# cdrbot.net
KiCad netlist of a schematic drawn in EAGLE
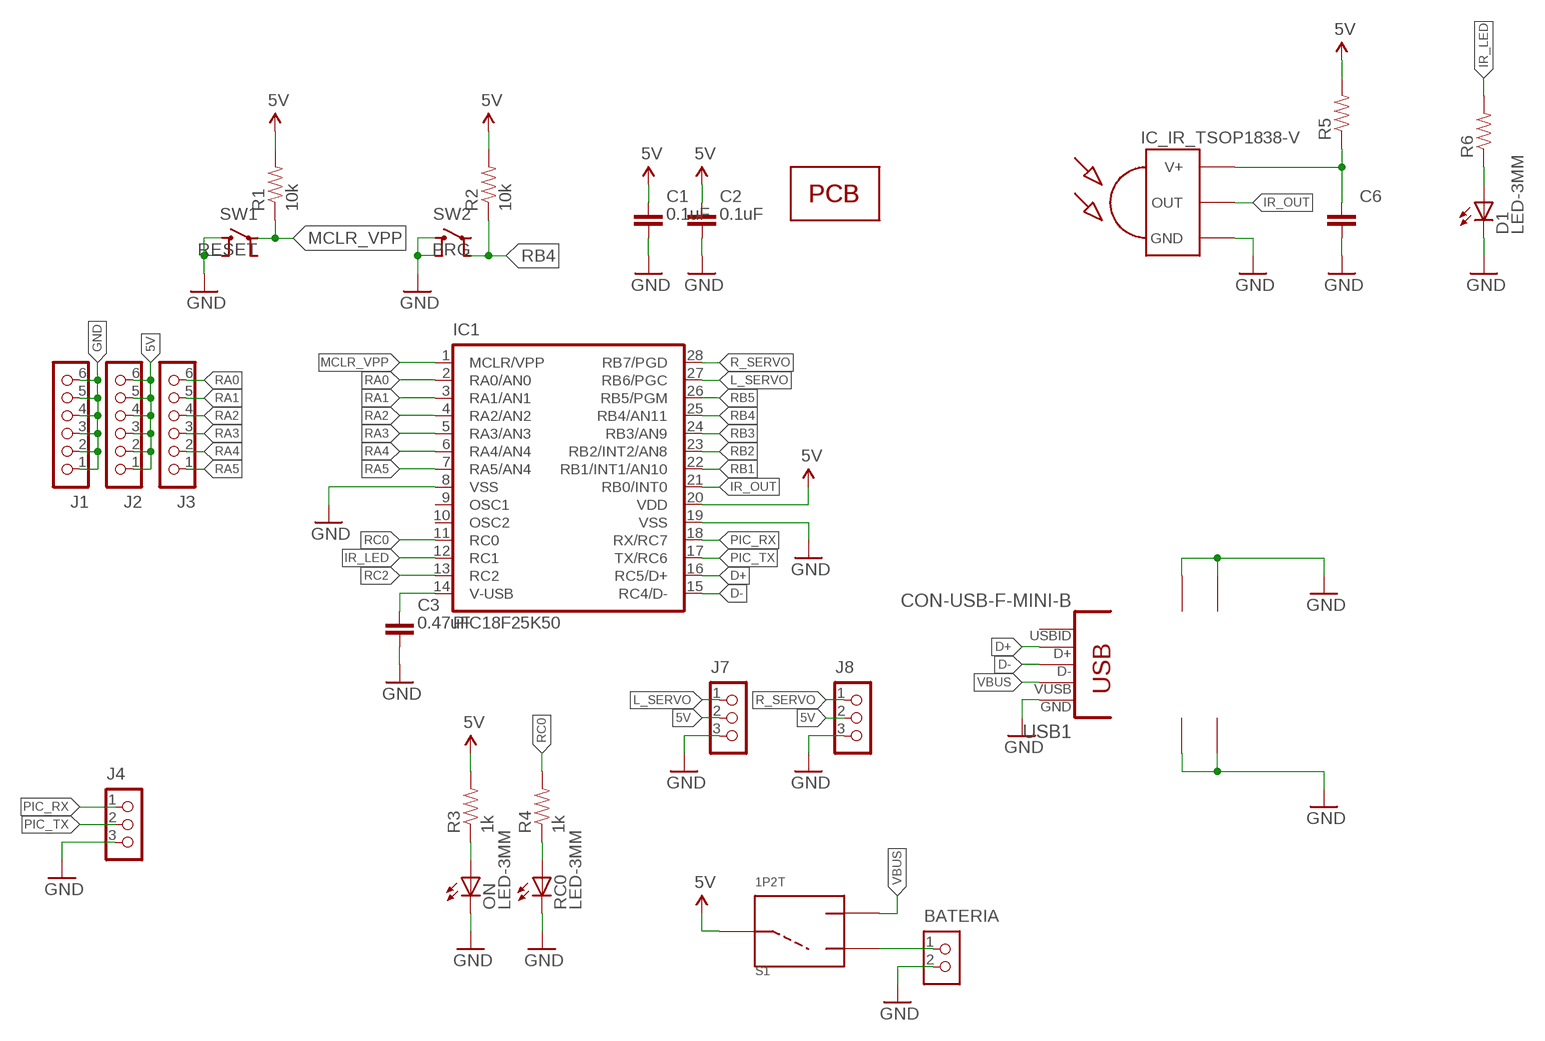
[diagram p0: schematic, sheet 1]

(export (version "E")
  (design (tool "Eeschema 10.0.6"))
  (components
    (comp (ref "BATERIA")
      (value "CON_HEADER_1X02-PTH-M")
      (footprint "eagle-import:M1X02_M")
      (libsource (lib "eagle-import") (part "CON_HEADER_1X02-PTH-M"))
    )
    (comp (ref "C1")
      (value "0.1uF")
      (footprint "eagle-import:C025-025X050")
      (libsource (lib "eagle-import") (part "CAPACITOR-DECOUPLING"))
    )
    (comp (ref "C2")
      (value "0.1uF")
      (footprint "eagle-import:C025-025X050")
      (libsource (lib "eagle-import") (part "CAPACITOR-DECOUPLING"))
    )
    (comp (ref "C3")
      (value "0.47uF")
      (footprint "eagle-import:C025-025X050")
      (libsource (lib "eagle-import") (part "CAPACITOR-DECOUPLING"))
    )
    (comp (ref "C6")
      (value "CAPACITOR-DECOUPLING")
      (footprint "eagle-import:C025-025X050")
      (libsource (lib "eagle-import") (part "CAPACITOR-DECOUPLING"))
    )
    (comp (ref "D1")
      (value "LED-3MM")
      (footprint "eagle-import:LED-3MM")
      (libsource (lib "eagle-import") (part "LED-3MM"))
    )
    (comp (ref "IC1")
      (value "PIC18F25K50")
      (footprint "eagle-import:DIL-28")
      (libsource (lib "eagle-import") (part "PIC18F2550"))
    )
    (comp (ref "IC2")
      (value "IC_IR_TSOP1838-V")
      (footprint "eagle-import:TSOP18XX_V")
      (libsource (lib "eagle-import") (part "IC_IR_TSOP1838-V"))
    )
    (comp (ref "J1")
      (value "CON_HEADER_1X06-PTH_M")
      (footprint "eagle-import:M1X06_M")
      (libsource (lib "eagle-import") (part "CON_HEADER_1X06-PTH_M"))
    )
    (comp (ref "J2")
      (value "CON_HEADER_1X06-PTH_M")
      (footprint "eagle-import:M1X06_M")
      (libsource (lib "eagle-import") (part "CON_HEADER_1X06-PTH_M"))
    )
    (comp (ref "J3")
      (value "CON_HEADER_1X06-PTH_M")
      (footprint "eagle-import:M1X06_M")
      (libsource (lib "eagle-import") (part "CON_HEADER_1X06-PTH_M"))
    )
    (comp (ref "J4")
      (value "CON_HEADER_1X03-PTH_M")
      (footprint "eagle-import:M1X03_M")
      (libsource (lib "eagle-import") (part "CON_HEADER_1X03-PTH_M"))
    )
    (comp (ref "J7")
      (value "CON_HEADER_1X03-PTH_M")
      (footprint "eagle-import:M1X03_M")
      (libsource (lib "eagle-import") (part "CON_HEADER_1X03-PTH_M"))
    )
    (comp (ref "J8")
      (value "CON_HEADER_1X03-PTH_M")
      (footprint "eagle-import:M1X03_M")
      (libsource (lib "eagle-import") (part "CON_HEADER_1X03-PTH_M"))
    )
    (comp (ref "ON")
      (value "LED-3MM")
      (footprint "eagle-import:LED-3MM")
      (libsource (lib "eagle-import") (part "LED-3MM"))
    )
    (comp (ref "PCB1")
      (value "PCB_DP_SQUARE-5X5")
      (footprint "eagle-import:PCB5X5")
      (libsource (lib "eagle-import") (part "PCB_DP_SQUARE-5X5"))
    )
    (comp (ref "R1")
      (value "10k")
      (footprint "eagle-import:RTH025W_03")
      (libsource (lib "eagle-import") (part "RESISTOR-1/4W-0.3{dblquote}"))
    )
    (comp (ref "R2")
      (value "10k")
      (footprint "eagle-import:RTH025W_03")
      (libsource (lib "eagle-import") (part "RESISTOR-1/4W-0.3{dblquote}"))
    )
    (comp (ref "R3")
      (value "1k")
      (footprint "eagle-import:RTH025W_03")
      (libsource (lib "eagle-import") (part "RESISTOR-1/4W-0.3{dblquote}"))
    )
    (comp (ref "R4")
      (value "1k")
      (footprint "eagle-import:RTH025W_03")
      (libsource (lib "eagle-import") (part "RESISTOR-1/4W-0.3{dblquote}"))
    )
    (comp (ref "R5")
      (value "RESISTOR-1/4W-0.3\"")
      (footprint "eagle-import:RTH025W_03")
      (libsource (lib "eagle-import") (part "RESISTOR-1/4W-0.3{dblquote}"))
    )
    (comp (ref "R6")
      (value "RESISTOR-1/4W-0.3\"")
      (footprint "eagle-import:RTH025W_03")
      (libsource (lib "eagle-import") (part "RESISTOR-1/4W-0.3{dblquote}"))
    )
    (comp (ref "RC0")
      (value "LED-3MM")
      (footprint "eagle-import:LED-3MM")
      (libsource (lib "eagle-import") (part "LED-3MM"))
    )
    (comp (ref "S1")
      (value "1P2T")
      (footprint "eagle-import:1P2T")
      (libsource (lib "eagle-import") (part "1P2T"))
    )
    (comp (ref "SW1")
      (value "RESET")
      (footprint "eagle-import:TACTILE-PTH")
      (libsource (lib "eagle-import") (part "SWITCH-MOMPTH"))
    )
    (comp (ref "SW2")
      (value "PRG")
      (footprint "eagle-import:TACTILE-PTH")
      (libsource (lib "eagle-import") (part "SWITCH-MOMPTH"))
    )
    (comp (ref "USB1")
      (value "CON-USB-F-MINI-B")
      (footprint "eagle-import:CONN_USB_MINI-B")
      (libsource (lib "eagle-import") (part "CON-USB-F-MINI-B"))
    )
  )
  (nets
    (net (code "1") (name "5V") (class "Default")
      (node (ref "C1") (pin "1") (pinfunction "1_1") (pintype "passive"))
      (node (ref "C2") (pin "1") (pinfunction "1_1") (pintype "passive"))
      (node (ref "IC1") (pin "20") (pinfunction "VDD_20") (pintype "power_in"))
      (node (ref "J2") (pin "1") (pinfunction "1_1") (pintype "bidirectional"))
      (node (ref "J2") (pin "2") (pinfunction "2_2") (pintype "bidirectional"))
      (node (ref "J2") (pin "3") (pinfunction "3_3") (pintype "bidirectional"))
      (node (ref "J2") (pin "4") (pinfunction "4_4") (pintype "bidirectional"))
      (node (ref "J2") (pin "5") (pinfunction "5_5") (pintype "bidirectional"))
      (node (ref "J2") (pin "6") (pinfunction "6_6") (pintype "bidirectional"))
      (node (ref "J7") (pin "2") (pinfunction "2_2") (pintype "bidirectional"))
      (node (ref "J8") (pin "2") (pinfunction "2_2") (pintype "bidirectional"))
      (node (ref "R1") (pin "2") (pinfunction "2_2") (pintype "passive"))
      (node (ref "R2") (pin "2") (pinfunction "2_2") (pintype "passive"))
      (node (ref "R3") (pin "2") (pinfunction "2_2") (pintype "passive"))
      (node (ref "R5") (pin "2") (pinfunction "2_2") (pintype "passive"))
      (node (ref "S1") (pin "P$1") (pinfunction "P$1_P$1") (pintype "bidirectional"))
    )
    (net (code "2") (name "D+") (class "Default")
      (node (ref "IC1") (pin "16") (pinfunction "RC5/D+_16") (pintype "bidirectional"))
      (node (ref "USB1") (pin "D+") (pinfunction "D+_D+") (pintype "bidirectional"))
    )
    (net (code "3") (name "D-") (class "Default")
      (node (ref "IC1") (pin "15") (pinfunction "RC4/D-_15") (pintype "bidirectional"))
      (node (ref "USB1") (pin "D-") (pinfunction "D-_D-") (pintype "bidirectional"))
    )
    (net (code "4") (name "GND") (class "Default")
      (node (ref "BATERIA") (pin "2") (pinfunction "2_2") (pintype "bidirectional"))
      (node (ref "C1") (pin "2") (pinfunction "2_2") (pintype "passive"))
      (node (ref "C2") (pin "2") (pinfunction "2_2") (pintype "passive"))
      (node (ref "C3") (pin "2") (pinfunction "2_2") (pintype "passive"))
      (node (ref "C6") (pin "2") (pinfunction "2_2") (pintype "passive"))
      (node (ref "D1") (pin "K") (pinfunction "C_K") (pintype "passive"))
      (node (ref "IC1") (pin "19") (pinfunction "VSS_19") (pintype "power_in"))
      (node (ref "IC1") (pin "8") (pinfunction "VSS_8") (pintype "power_in"))
      (node (ref "IC2") (pin "GND") (pinfunction "GND_GND") (pintype "bidirectional"))
      (node (ref "J1") (pin "1") (pinfunction "1_1") (pintype "bidirectional"))
      (node (ref "J1") (pin "2") (pinfunction "2_2") (pintype "bidirectional"))
      (node (ref "J1") (pin "3") (pinfunction "3_3") (pintype "bidirectional"))
      (node (ref "J1") (pin "4") (pinfunction "4_4") (pintype "bidirectional"))
      (node (ref "J1") (pin "5") (pinfunction "5_5") (pintype "bidirectional"))
      (node (ref "J1") (pin "6") (pinfunction "6_6") (pintype "bidirectional"))
      (node (ref "J4") (pin "3") (pinfunction "3_3") (pintype "bidirectional"))
      (node (ref "J7") (pin "3") (pinfunction "3_3") (pintype "bidirectional"))
      (node (ref "J8") (pin "3") (pinfunction "3_3") (pintype "bidirectional"))
      (node (ref "ON") (pin "K") (pinfunction "C_K") (pintype "passive"))
      (node (ref "RC0") (pin "K") (pinfunction "C_K") (pintype "passive"))
      (node (ref "SW1") (pin "3") (pinfunction "2_3") (pintype "passive"))
      (node (ref "SW1") (pin "4") (pinfunction "4_4") (pintype "passive"))
      (node (ref "SW2") (pin "3") (pinfunction "2_3") (pintype "passive"))
      (node (ref "SW2") (pin "4") (pinfunction "4_4") (pintype "passive"))
      (node (ref "USB1") (pin "BODY@1") (pinfunction "BODY_BODY@1") (pintype "tri_state"))
      (node (ref "USB1") (pin "BODY@2") (pinfunction "BODY_BODY@2") (pintype "tri_state"))
      (node (ref "USB1") (pin "BODY@3") (pinfunction "BODY_BODY@3") (pintype "tri_state"))
      (node (ref "USB1") (pin "BODY@4") (pinfunction "BODY_BODY@4") (pintype "tri_state"))
      (node (ref "USB1") (pin "GND") (pinfunction "GND_GND") (pintype "bidirectional"))
    )
    (net (code "5") (name "IR_LED") (class "Default")
      (node (ref "IC1") (pin "12") (pinfunction "RC1_12") (pintype "bidirectional"))
      (node (ref "R6") (pin "2") (pinfunction "2_2") (pintype "passive"))
    )
    (net (code "6") (name "IR_OUT") (class "Default")
      (node (ref "IC1") (pin "21") (pinfunction "RB0/INT0_21") (pintype "bidirectional"))
      (node (ref "IC2") (pin "OUT") (pinfunction "OUT_OUT") (pintype "bidirectional"))
    )
    (net (code "7") (name "L_SERVO") (class "Default")
      (node (ref "IC1") (pin "27") (pinfunction "RB6/PGC_27") (pintype "bidirectional"))
      (node (ref "J7") (pin "1") (pinfunction "1_1") (pintype "bidirectional"))
    )
    (net (code "8") (name "MCLR_VPP") (class "Default")
      (node (ref "IC1") (pin "1") (pinfunction "MCLR/VPP_1") (pintype "bidirectional"))
      (node (ref "R1") (pin "1") (pinfunction "1_1") (pintype "passive"))
      (node (ref "SW1") (pin "1") (pinfunction "1_1") (pintype "passive"))
    )
    (net (code "9") (name "Net-(BATERIA-Pad1)") (class "Default")
      (node (ref "BATERIA") (pin "1") (pinfunction "1_1") (pintype "bidirectional"))
      (node (ref "S1") (pin "P$2") (pinfunction "P$2_P$2") (pintype "bidirectional"))
    )
    (net (code "10") (name "Net-(D1-PadA)") (class "Default")
      (node (ref "D1") (pin "A") (pinfunction "A_A") (pintype "passive"))
      (node (ref "R6") (pin "1") (pinfunction "1_1") (pintype "passive"))
    )
    (net (code "11") (name "Net-(IC1-V-USB)") (class "Default")
      (node (ref "C3") (pin "1") (pinfunction "1_1") (pintype "passive"))
      (node (ref "IC1") (pin "14") (pinfunction "V-USB_14") (pintype "bidirectional"))
    )
    (net (code "12") (name "Net-(IC2-V+)") (class "Default")
      (node (ref "C6") (pin "1") (pinfunction "1_1") (pintype "passive"))
      (node (ref "IC2") (pin "VCC") (pinfunction "V+_VCC") (pintype "bidirectional"))
      (node (ref "R5") (pin "1") (pinfunction "1_1") (pintype "passive"))
    )
    (net (code "13") (name "Net-(ON-PadA)") (class "Default")
      (node (ref "ON") (pin "A") (pinfunction "A_A") (pintype "passive"))
      (node (ref "R3") (pin "1") (pinfunction "1_1") (pintype "passive"))
    )
    (net (code "14") (name "Net-(R4-Pad1)") (class "Default")
      (node (ref "R4") (pin "1") (pinfunction "1_1") (pintype "passive"))
      (node (ref "RC0") (pin "A") (pinfunction "A_A") (pintype "passive"))
    )
    (net (code "15") (name "PIC_RX") (class "Default")
      (node (ref "IC1") (pin "18") (pinfunction "RX/RC7_18") (pintype "input"))
      (node (ref "J4") (pin "1") (pinfunction "1_1") (pintype "bidirectional"))
    )
    (net (code "16") (name "PIC_TX") (class "Default")
      (node (ref "IC1") (pin "17") (pinfunction "TX/RC6_17") (pintype "bidirectional"))
      (node (ref "J4") (pin "2") (pinfunction "2_2") (pintype "bidirectional"))
    )
    (net (code "17") (name "RA0") (class "Default")
      (node (ref "IC1") (pin "2") (pinfunction "RA0/AN0_2") (pintype "bidirectional"))
      (node (ref "J3") (pin "6") (pinfunction "6_6") (pintype "bidirectional"))
    )
    (net (code "18") (name "RA1") (class "Default")
      (node (ref "IC1") (pin "3") (pinfunction "RA1/AN1_3") (pintype "bidirectional"))
      (node (ref "J3") (pin "5") (pinfunction "5_5") (pintype "bidirectional"))
    )
    (net (code "19") (name "RA2") (class "Default")
      (node (ref "IC1") (pin "4") (pinfunction "RA2/AN2_4") (pintype "bidirectional"))
      (node (ref "J3") (pin "4") (pinfunction "4_4") (pintype "bidirectional"))
    )
    (net (code "20") (name "RA3") (class "Default")
      (node (ref "IC1") (pin "5") (pinfunction "RA3/AN3_5") (pintype "bidirectional"))
      (node (ref "J3") (pin "3") (pinfunction "3_3") (pintype "bidirectional"))
    )
    (net (code "21") (name "RA4") (class "Default")
      (node (ref "IC1") (pin "6") (pinfunction "RA4/AN4_6") (pintype "bidirectional"))
      (node (ref "J3") (pin "2") (pinfunction "2_2") (pintype "bidirectional"))
    )
    (net (code "22") (name "RA5") (class "Default")
      (node (ref "IC1") (pin "7") (pinfunction "RA5/AN4_7") (pintype "bidirectional"))
      (node (ref "J3") (pin "1") (pinfunction "1_1") (pintype "bidirectional"))
    )
    (net (code "23") (name "RB1") (class "Default")
      (node (ref "IC1") (pin "22") (pinfunction "RB1/INT1/AN10_22") (pintype "bidirectional"))
    )
    (net (code "24") (name "RB2") (class "Default")
      (node (ref "IC1") (pin "23") (pinfunction "RB2/INT2/AN8_23") (pintype "bidirectional"))
    )
    (net (code "25") (name "RB3") (class "Default")
      (node (ref "IC1") (pin "24") (pinfunction "RB3/AN9_24") (pintype "bidirectional"))
    )
    (net (code "26") (name "RB4") (class "Default")
      (node (ref "IC1") (pin "25") (pinfunction "RB4/AN11_25") (pintype "bidirectional"))
      (node (ref "R2") (pin "1") (pinfunction "1_1") (pintype "passive"))
      (node (ref "SW2") (pin "2") (pinfunction "3_2") (pintype "passive"))
    )
    (net (code "27") (name "RB5") (class "Default")
      (node (ref "IC1") (pin "26") (pinfunction "RB5/PGM_26") (pintype "bidirectional"))
    )
    (net (code "28") (name "RC0") (class "Default")
      (node (ref "IC1") (pin "11") (pinfunction "RC0_11") (pintype "bidirectional"))
      (node (ref "R4") (pin "2") (pinfunction "2_2") (pintype "passive"))
    )
    (net (code "29") (name "RC2") (class "Default")
      (node (ref "IC1") (pin "13") (pinfunction "RC2_13") (pintype "bidirectional"))
    )
    (net (code "30") (name "R_SERVO") (class "Default")
      (node (ref "IC1") (pin "28") (pinfunction "RB7/PGD_28") (pintype "bidirectional"))
      (node (ref "J8") (pin "1") (pinfunction "1_1") (pintype "bidirectional"))
    )
    (net (code "31") (name "VBUS") (class "Default")
      (node (ref "S1") (pin "P$3") (pinfunction "P$3_P$3") (pintype "bidirectional"))
      (node (ref "USB1") (pin "VUSB") (pinfunction "VUSB_VUSB") (pintype "bidirectional"))
    )
    (net (code "32") (name "unconnected-(IC1-OSC1-Pad9)") (class "Default")
      (node (ref "IC1") (pin "9") (pinfunction "OSC1_9") (pintype "bidirectional"))
    )
    (net (code "33") (name "unconnected-(IC1-OSC2-Pad10)") (class "Default")
      (node (ref "IC1") (pin "10") (pinfunction "OSC2_10") (pintype "bidirectional"))
    )
    (net (code "34") (name "unconnected-(SW1-3-Pad2)") (class "Default")
      (node (ref "SW1") (pin "2") (pinfunction "3_2") (pintype "passive"))
    )
    (net (code "35") (name "unconnected-(SW2-Pad1)") (class "Default")
      (node (ref "SW2") (pin "1") (pinfunction "1_1") (pintype "passive"))
    )
    (net (code "36") (name "unconnected-(USB1B-USBID-PadID)") (class "Default")
      (node (ref "USB1") (pin "ID") (pinfunction "USBID_ID") (pintype "bidirectional"))
    )
  )
)
